# am.net
KiCad netlist of a schematic drawn in EAGLE
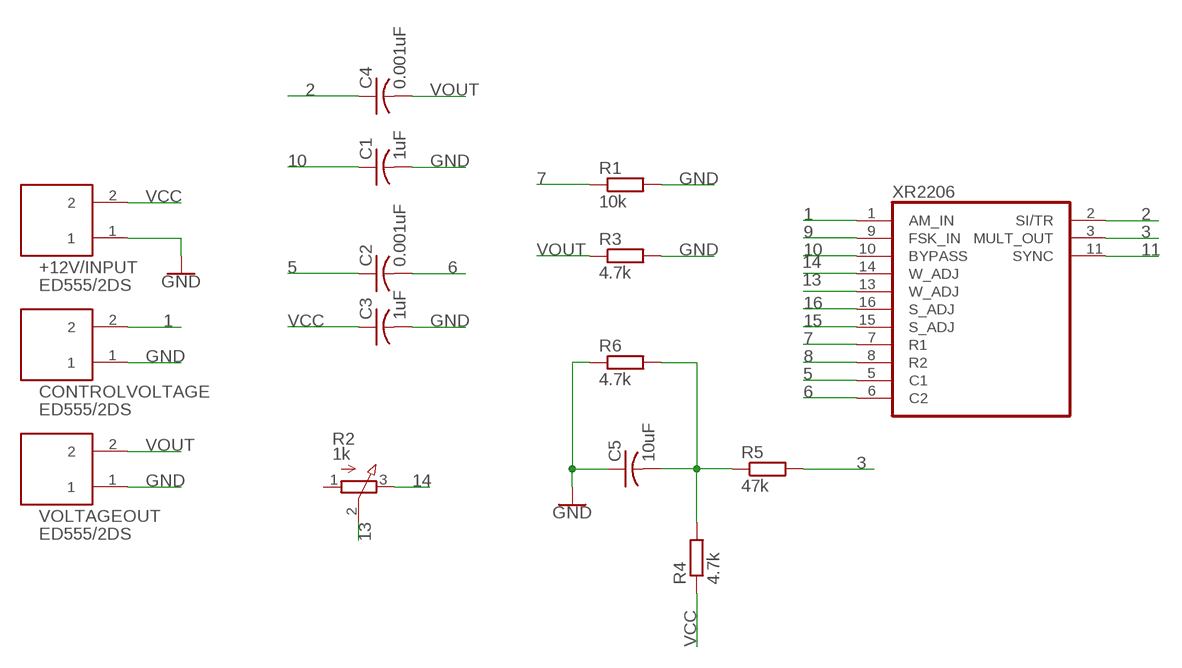
[diagram p0: schematic, sheet 1]

(export (version "E")
  (design (tool "Eeschema 10.0.6"))
  (components
    (comp (ref "+12V/INPUT")
      (value "ED555/2DS")
      (footprint "eagle-import:ED555_2DS")
      (libsource (lib "eagle-import") (part "ED555/2DS"))
    )
    (comp (ref "C1")
      (value "1uF")
      (footprint "eagle-import:C050-030X075")
      (libsource (lib "eagle-import") (part "C-US050-030X075"))
    )
    (comp (ref "C2")
      (value "0.001uF")
      (footprint "eagle-import:C050-030X075")
      (libsource (lib "eagle-import") (part "C-US050-030X075"))
    )
    (comp (ref "C3")
      (value "1uF")
      (footprint "eagle-import:C050-030X075")
      (libsource (lib "eagle-import") (part "C-US050-030X075"))
    )
    (comp (ref "C4")
      (value "0.001uF")
      (footprint "eagle-import:C050-030X075")
      (libsource (lib "eagle-import") (part "C-US050-030X075"))
    )
    (comp (ref "C5")
      (value "10uF")
      (footprint "eagle-import:C050-030X075")
      (libsource (lib "eagle-import") (part "C-US050-030X075"))
    )
    (comp (ref "CONTROLVOLTAGE")
      (value "ED555/2DS")
      (footprint "eagle-import:ED555_2DS")
      (libsource (lib "eagle-import") (part "ED555/2DS"))
    )
    (comp (ref "R1")
      (value "10k")
      (footprint "eagle-import:0207_10")
      (libsource (lib "eagle-import") (part "R-EU_0207/10"))
    )
    (comp (ref "R2")
      (value "1k")
      (footprint "eagle-import:3RP_1610N")
      (libsource (lib "eagle-import") (part "3RP/1610N"))
    )
    (comp (ref "R3")
      (value "4.7k")
      (footprint "eagle-import:0207_10")
      (libsource (lib "eagle-import") (part "R-EU_0207/10"))
    )
    (comp (ref "R4")
      (value "4.7k")
      (footprint "eagle-import:0207_10")
      (libsource (lib "eagle-import") (part "R-EU_0207/10"))
    )
    (comp (ref "R5")
      (value "47k")
      (footprint "eagle-import:0207_10")
      (libsource (lib "eagle-import") (part "R-EU_0207/10"))
    )
    (comp (ref "R6")
      (value "4.7k")
      (footprint "eagle-import:0207_10")
      (libsource (lib "eagle-import") (part "R-EU_0207/10"))
    )
    (comp (ref "VOLTAGEOUT")
      (value "ED555/2DS")
      (footprint "eagle-import:ED555_2DS")
      (libsource (lib "eagle-import") (part "ED555/2DS"))
    )
    (comp (ref "XR2206")
      (value "XR-2206")
      (footprint "eagle-import:DIL16")
      (libsource (lib "eagle-import") (part "XR-2206"))
    )
  )
  (nets
    (net (code "1") (name "/1") (class "Default")
      (node (ref "CONTROLVOLTAGE") (pin "2") (pinfunction "2_2") (pintype "bidirectional"))
      (node (ref "XR2206") (pin "1") (pinfunction "AM_IN_1") (pintype "input"))
    )
    (net (code "2") (name "/2") (class "Default")
      (node (ref "C4") (pin "1") (pinfunction "1_1") (pintype "passive"))
      (node (ref "XR2206") (pin "2") (pinfunction "SI/TR_2") (pintype "output"))
    )
    (net (code "3") (name "/3") (class "Default")
      (node (ref "R5") (pin "2") (pinfunction "2_2") (pintype "passive"))
      (node (ref "XR2206") (pin "3") (pinfunction "MULT_OUT_3") (pintype "output"))
    )
    (net (code "4") (name "/5") (class "Default")
      (node (ref "C2") (pin "1") (pinfunction "1_1") (pintype "passive"))
      (node (ref "XR2206") (pin "5") (pinfunction "C1_5") (pintype "input"))
    )
    (net (code "5") (name "/6") (class "Default")
      (node (ref "C2") (pin "2") (pinfunction "2_2") (pintype "passive"))
      (node (ref "XR2206") (pin "6") (pinfunction "C2_6") (pintype "input"))
    )
    (net (code "6") (name "/7") (class "Default")
      (node (ref "R1") (pin "1") (pinfunction "1_1") (pintype "passive"))
      (node (ref "XR2206") (pin "7") (pinfunction "R1_7") (pintype "input"))
    )
    (net (code "7") (name "/8") (class "Default")
      (node (ref "XR2206") (pin "8") (pinfunction "R2_8") (pintype "input"))
    )
    (net (code "8") (name "/9") (class "Default")
      (node (ref "XR2206") (pin "9") (pinfunction "FSK_IN_9") (pintype "input"))
    )
    (net (code "9") (name "/10") (class "Default")
      (node (ref "C1") (pin "1") (pinfunction "1_1") (pintype "passive"))
      (node (ref "XR2206") (pin "10") (pinfunction "BYPASS_10") (pintype "input"))
    )
    (net (code "10") (name "/11") (class "Default")
      (node (ref "XR2206") (pin "11") (pinfunction "SYNC_11") (pintype "output"))
    )
    (net (code "11") (name "/13") (class "Default")
      (node (ref "R2") (pin "2") (pinfunction "S_2") (pintype "passive"))
      (node (ref "XR2206") (pin "13") (pinfunction "W_ADJ_13") (pintype "input"))
    )
    (net (code "12") (name "/14") (class "Default")
      (node (ref "R2") (pin "3") (pinfunction "E_3") (pintype "passive"))
      (node (ref "XR2206") (pin "14") (pinfunction "W_ADJ_14") (pintype "input"))
    )
    (net (code "13") (name "/15") (class "Default")
      (node (ref "XR2206") (pin "15") (pinfunction "S_ADJ_15") (pintype "input"))
    )
    (net (code "14") (name "/16") (class "Default")
      (node (ref "XR2206") (pin "16") (pinfunction "S_ADJ_16") (pintype "input"))
    )
    (net (code "15") (name "/VCC") (class "Default")
      (node (ref "+12V/INPUT") (pin "2") (pinfunction "2_2") (pintype "bidirectional"))
      (node (ref "C3") (pin "1") (pinfunction "1_1") (pintype "passive"))
      (node (ref "R4") (pin "1") (pinfunction "1_1") (pintype "passive"))
    )
    (net (code "16") (name "/VOUT") (class "Default")
      (node (ref "C4") (pin "2") (pinfunction "2_2") (pintype "passive"))
      (node (ref "R3") (pin "1") (pinfunction "1_1") (pintype "passive"))
      (node (ref "VOLTAGEOUT") (pin "2") (pinfunction "2_2") (pintype "bidirectional"))
    )
    (net (code "17") (name "GND") (class "Default")
      (node (ref "+12V/INPUT") (pin "1") (pinfunction "1_1") (pintype "bidirectional"))
      (node (ref "C1") (pin "2") (pinfunction "2_2") (pintype "passive"))
      (node (ref "C3") (pin "2") (pinfunction "2_2") (pintype "passive"))
      (node (ref "C5") (pin "1") (pinfunction "1_1") (pintype "passive"))
      (node (ref "CONTROLVOLTAGE") (pin "1") (pinfunction "1_1") (pintype "bidirectional"))
      (node (ref "R1") (pin "2") (pinfunction "2_2") (pintype "passive"))
      (node (ref "R3") (pin "2") (pinfunction "2_2") (pintype "passive"))
      (node (ref "R6") (pin "1") (pinfunction "1_1") (pintype "passive"))
      (node (ref "VOLTAGEOUT") (pin "1") (pinfunction "1_1") (pintype "bidirectional"))
    )
    (net (code "18") (name "Net-(C5-Pad2)") (class "Default")
      (node (ref "C5") (pin "2") (pinfunction "2_2") (pintype "passive"))
      (node (ref "R4") (pin "2") (pinfunction "2_2") (pintype "passive"))
      (node (ref "R5") (pin "1") (pinfunction "1_1") (pintype "passive"))
      (node (ref "R6") (pin "2") (pinfunction "2_2") (pintype "passive"))
    )
    (net (code "19") (name "unconnected-(R2-A-Pad1)") (class "Default")
      (node (ref "R2") (pin "1") (pinfunction "A_1") (pintype "passive"))
    )
  )
)
